# LTC_Sheet.net
KiCad netlist of a schematic drawn in Altium Designer
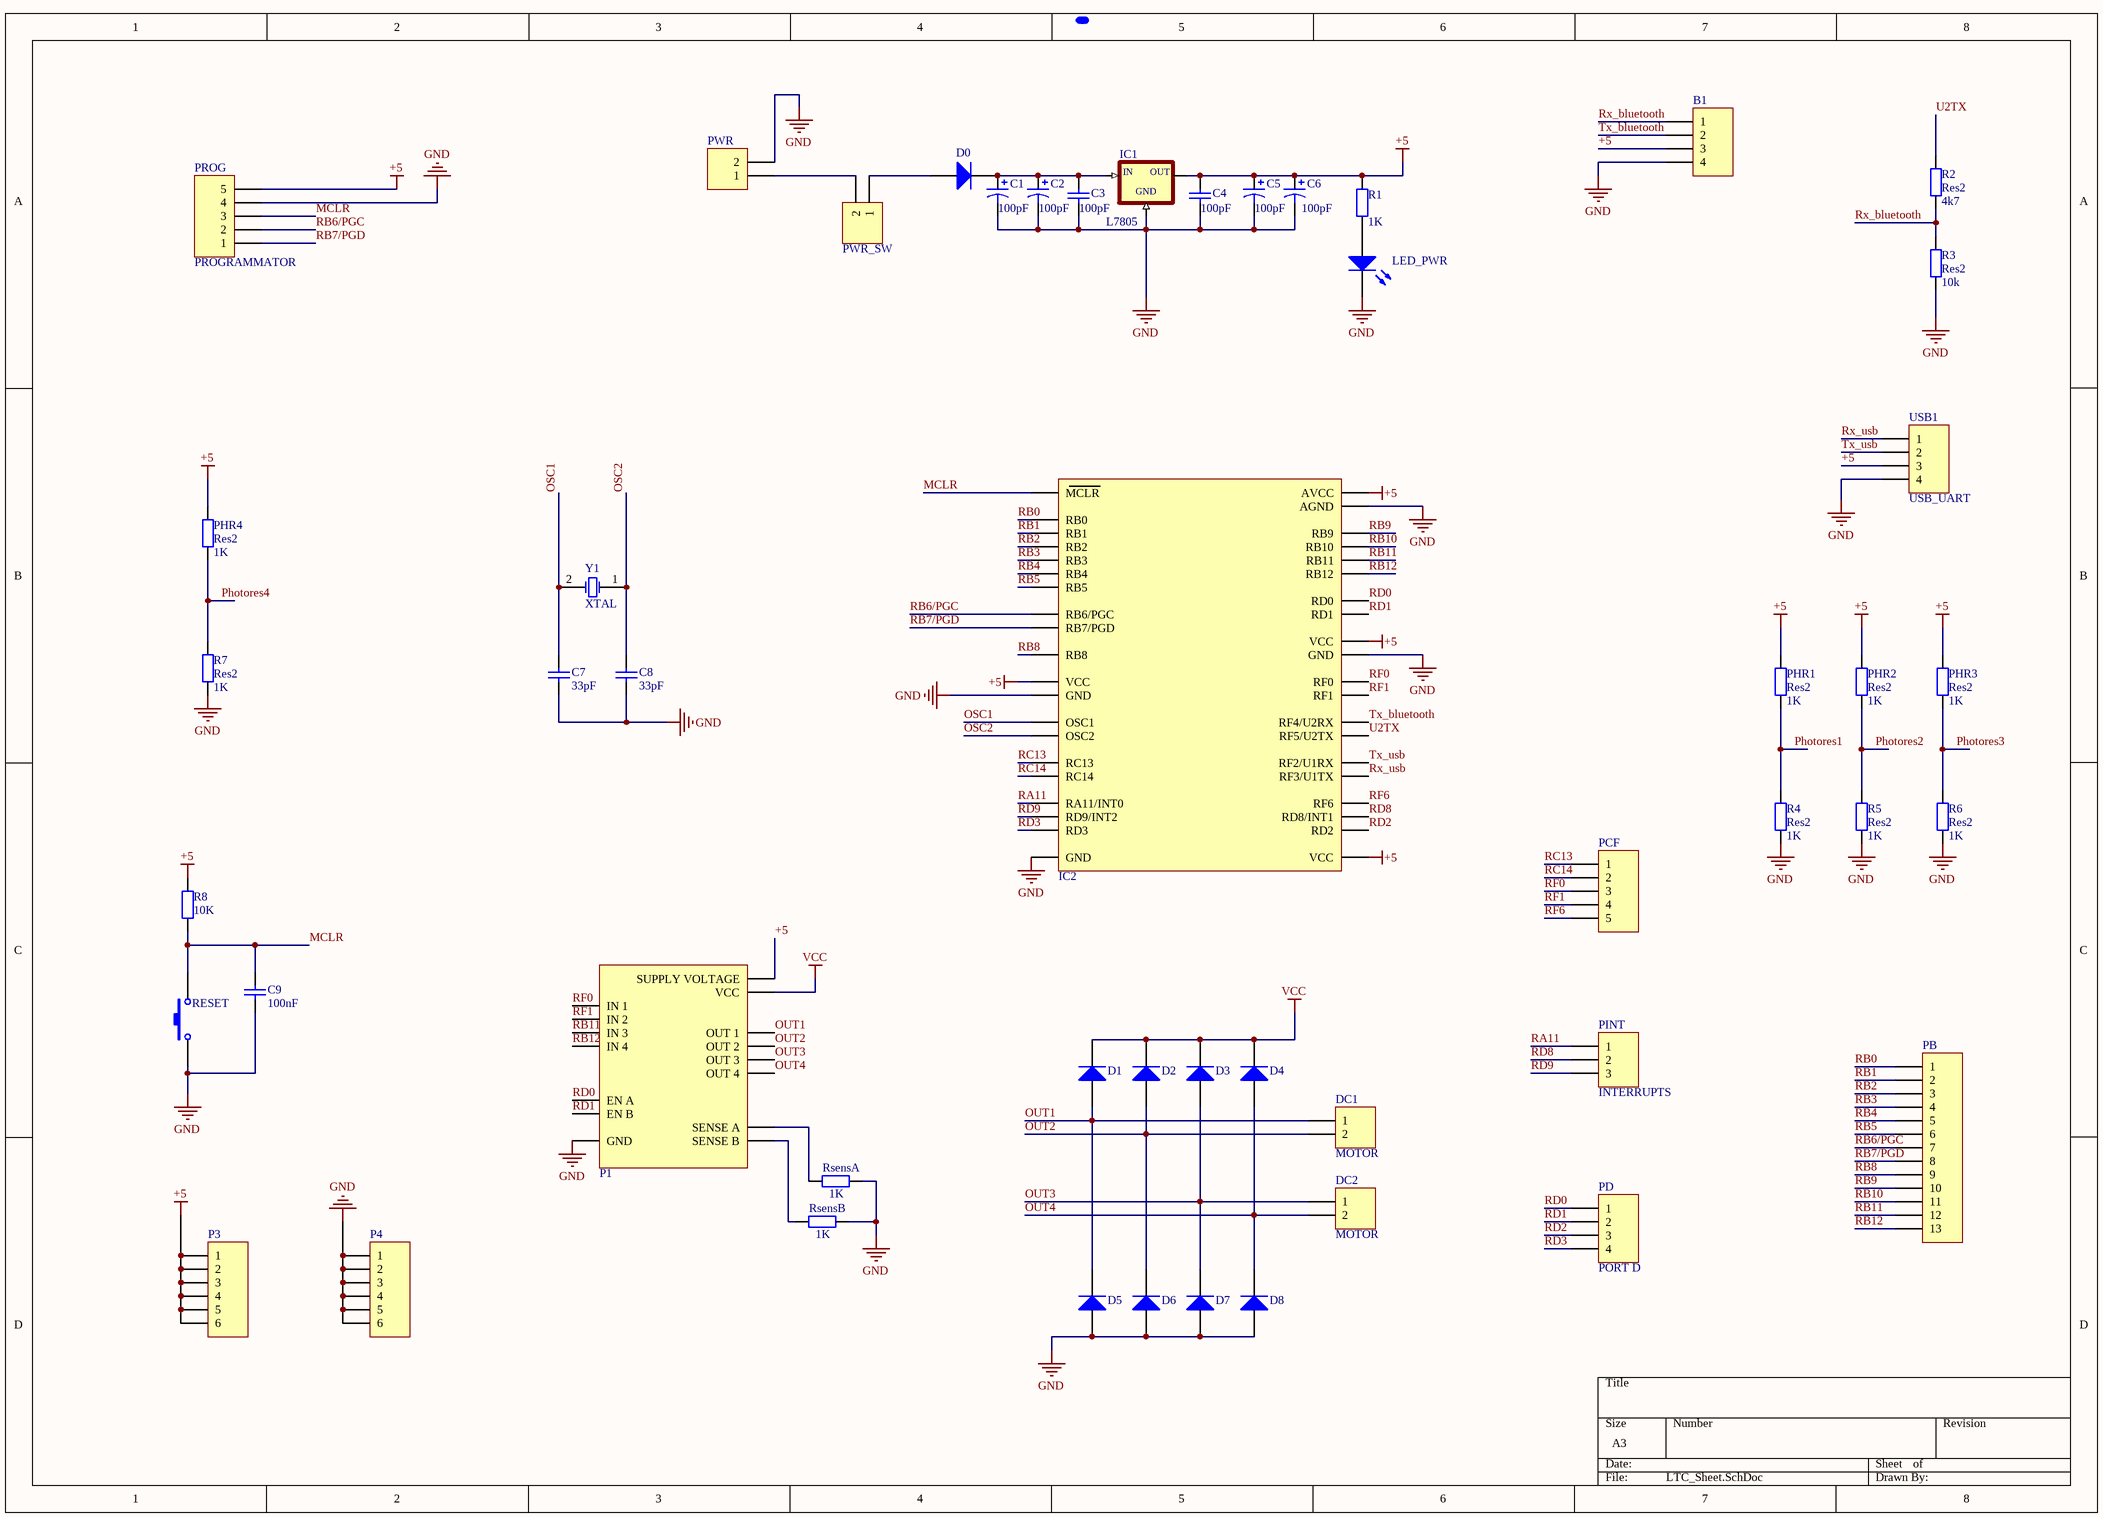
[diagram p0: LTC_Sheet.SchDoc]

(export (version "E")
  (design (tool "Eeschema 10.0.6"))
  (components
    (comp (ref "B1")
      (value "~")
      (footprint "HDR1X4")
      (description "Header, 4-Pin")
      (fields (field (name "PUBLISHER") "Altium Limited"))
      (libsource (lib "Miscellaneous Connectors") (part "Header 4"))
    )
    (comp (ref "C1")
      (value "100pF")
      (footprint "RB7.6-15")
      (description "Polarized Capacitor (Radial)")
      (fields (field (name "PUBLISHER") "Altium Limited"))
      (libsource (lib "Miscellaneous Devices") (part "Cap Pol1"))
    )
    (comp (ref "C2")
      (value "100pF")
      (footprint "RB7.6-15")
      (description "Polarized Capacitor (Radial)")
      (fields (field (name "PUBLISHER") "Altium Limited"))
      (libsource (lib "Miscellaneous Devices") (part "Cap Pol1"))
    )
    (comp (ref "C3")
      (value "100pF")
      (footprint "RAD-0.3")
      (description "Capacitor")
      (fields (field (name "PUBLISHER") "Altium Limited"))
      (libsource (lib "Miscellaneous Devices") (part "Cap"))
    )
    (comp (ref "C4")
      (value "100pF")
      (footprint "RAD-0.3")
      (description "Capacitor")
      (fields (field (name "PUBLISHER") "Altium Limited"))
      (libsource (lib "Miscellaneous Devices") (part "Cap"))
    )
    (comp (ref "C5")
      (value "100pF")
      (footprint "RB7.6-15")
      (description "Polarized Capacitor (Radial)")
      (fields (field (name "PUBLISHER") "Altium Limited"))
      (libsource (lib "Miscellaneous Devices") (part "Cap Pol1"))
    )
    (comp (ref "C6")
      (value "100pF")
      (footprint "RB7.6-15")
      (description "Polarized Capacitor (Radial)")
      (fields (field (name "PUBLISHER") "Altium Limited"))
      (libsource (lib "Miscellaneous Devices") (part "Cap Pol1"))
    )
    (comp (ref "C7")
      (value "33pF")
      (footprint "RAD-0.3")
      (description "Capacitor")
      (fields (field (name "Comment") "Cap") (field (name "PUBLISHER") "Altium Limited"))
      (libsource (lib "Miscellaneous Devices") (part "Cap"))
    )
    (comp (ref "C8")
      (value "33pF")
      (footprint "RAD-0.3")
      (description "Capacitor")
      (fields (field (name "Comment") "Cap") (field (name "PUBLISHER") "Altium Limited"))
      (libsource (lib "Miscellaneous Devices") (part "Cap"))
    )
    (comp (ref "C9")
      (value "100nF")
      (footprint "RAD-0.3")
      (description "Capacitor")
      (fields (field (name "Comment") "Cap") (field (name "PUBLISHER") "Altium Limited"))
      (libsource (lib "Miscellaneous Devices") (part "Cap"))
    )
    (comp (ref "D0")
      (value "~")
      (footprint "DO-41")
      (description "1 Amp General Purpose Rectifier")
      (fields (field (name "PUBLISHER") "Altium Limited"))
      (libsource (lib "Miscellaneous Devices") (part "Diode 1N4007"))
    )
    (comp (ref "D1")
      (value "Diode 1N914")
      (footprint "DO-35")
      (description "High Conductance Fast Diode")
      (fields (field (name "PUBLISHER") "Altium Limited"))
      (libsource (lib "Miscellaneous Devices") (part "Diode 1N914"))
    )
    (comp (ref "D2")
      (value "Diode 1N914")
      (footprint "DO-35")
      (description "High Conductance Fast Diode")
      (fields (field (name "PUBLISHER") "Altium Limited"))
      (libsource (lib "Miscellaneous Devices") (part "Diode 1N914"))
    )
    (comp (ref "D3")
      (value "Diode 1N914")
      (footprint "DO-35")
      (description "High Conductance Fast Diode")
      (fields (field (name "PUBLISHER") "Altium Limited"))
      (libsource (lib "Miscellaneous Devices") (part "Diode 1N914"))
    )
    (comp (ref "D4")
      (value "Diode 1N914")
      (footprint "DO-35")
      (description "High Conductance Fast Diode")
      (fields (field (name "PUBLISHER") "Altium Limited"))
      (libsource (lib "Miscellaneous Devices") (part "Diode 1N914"))
    )
    (comp (ref "D5")
      (value "Diode 1N914")
      (footprint "DO-35")
      (description "High Conductance Fast Diode")
      (fields (field (name "PUBLISHER") "Altium Limited"))
      (libsource (lib "Miscellaneous Devices") (part "Diode 1N914"))
    )
    (comp (ref "D6")
      (value "Diode 1N914")
      (footprint "DO-35")
      (description "High Conductance Fast Diode")
      (fields (field (name "PUBLISHER") "Altium Limited"))
      (libsource (lib "Miscellaneous Devices") (part "Diode 1N914"))
    )
    (comp (ref "D7")
      (value "Diode 1N914")
      (footprint "DO-35")
      (description "High Conductance Fast Diode")
      (fields (field (name "PUBLISHER") "Altium Limited"))
      (libsource (lib "Miscellaneous Devices") (part "Diode 1N914"))
    )
    (comp (ref "D8")
      (value "Diode 1N914")
      (footprint "DO-35")
      (description "High Conductance Fast Diode")
      (fields (field (name "PUBLISHER") "Altium Limited"))
      (libsource (lib "Miscellaneous Devices") (part "Diode 1N914"))
    )
    (comp (ref "DC1")
      (value "MOTOR")
      (footprint "HDR1X2")
      (description "Header, 2-Pin")
      (fields (field (name "PUBLISHER") "Altium Limited"))
      (libsource (lib "") (part "Header 2_2"))
    )
    (comp (ref "DC2")
      (value "MOTOR")
      (footprint "HDR1X2")
      (description "Header, 2-Pin")
      (fields (field (name "PUBLISHER") "Altium Limited"))
      (libsource (lib "") (part "Header 2_2"))
    )
    (comp (ref "IC1")
      (value "L7805")
      (footprint "78XXS")
      (description "Linear Voltage Regulator IC 1 Output 1.5A D2PAK")
      (fields (field (name "MF") "STMicroelectronics"))
      (libsource (lib "L7805") (part "L7805"))
    )
    (comp (ref "IC2") (value "dsPIC30F4013") (libsource (lib "LibLTC") (part "IC_40")))
    (comp (ref "LED_PWR")
      (value "~")
      (footprint "LED-1")
      (description "Typical RED GaAs LED")
      (fields (field (name "PUBLISHER") "Altium Limited"))
      (libsource (lib "Miscellaneous Devices") (part "LED1"))
    )
    (comp (ref "P1") (value "L298N") (libsource (lib "LibRC") (part "L298N")))
    (comp (ref "P3")
      (value "~")
      (footprint "HDR1X6")
      (description "Header, 6-Pin")
      (fields (field (name "PUBLISHER") "Altium Limited"))
      (libsource (lib "Miscellaneous Connectors") (part "Header 6"))
    )
    (comp (ref "P4")
      (value "~")
      (footprint "HDR1X6")
      (description "Header, 6-Pin")
      (fields (field (name "PUBLISHER") "Altium Limited"))
      (libsource (lib "Miscellaneous Connectors") (part "Header 6"))
    )
    (comp (ref "PB")
      (value "~")
      (footprint "HDR1X13")
      (description "Header, 13-Pin")
      (fields (field (name "PUBLISHER") "Altium Limited"))
      (libsource (lib "Miscellaneous Connectors") (part "Header 13"))
    )
    (comp (ref "PCF")
      (value "~")
      (footprint "HDR1X5")
      (description "Header, 5-Pin")
      (fields (field (name "PUBLISHER") "Altium Limited"))
      (libsource (lib "") (part "Header 5_1"))
    )
    (comp (ref "PD")
      (value "PORT D")
      (footprint "HDR1X4")
      (description "Header, 4-Pin")
      (fields (field (name "PUBLISHER") "Altium Limited"))
      (libsource (lib "Miscellaneous Connectors") (part "Header 4"))
    )
    (comp (ref "PHR1")
      (value "Res2")
      (footprint "AXIAL-0.4")
      (description "Resistor")
      (fields (field (name "ALTIUM_VALUE") "1K") (field (name "PUBLISHER") "Altium Limited"))
      (libsource (lib "Miscellaneous Devices") (part "Res2"))
    )
    (comp (ref "PHR2")
      (value "Res2")
      (footprint "AXIAL-0.4")
      (description "Resistor")
      (fields (field (name "ALTIUM_VALUE") "1K") (field (name "PUBLISHER") "Altium Limited"))
      (libsource (lib "Miscellaneous Devices") (part "Res2"))
    )
    (comp (ref "PHR3")
      (value "Res2")
      (footprint "AXIAL-0.4")
      (description "Resistor")
      (fields (field (name "ALTIUM_VALUE") "1K") (field (name "PUBLISHER") "Altium Limited"))
      (libsource (lib "Miscellaneous Devices") (part "Res2"))
    )
    (comp (ref "PHR4")
      (value "Res2")
      (footprint "AXIAL-0.4")
      (description "Resistor")
      (fields (field (name "ALTIUM_VALUE") "1K") (field (name "PUBLISHER") "Altium Limited"))
      (libsource (lib "Miscellaneous Devices") (part "Res2"))
    )
    (comp (ref "PINT")
      (value "INTERRUPTS")
      (footprint "HDR1X3")
      (description "Header, 3-Pin")
      (fields (field (name "PUBLISHER") "Altium Limited"))
      (libsource (lib "Miscellaneous Connectors") (part "Header 3"))
    )
    (comp (ref "PROG")
      (value "PROGRAMMATOR")
      (footprint "HDR1X5")
      (description "Header, 5-Pin")
      (fields (field (name "PUBLISHER") "Altium Limited"))
      (libsource (lib "Miscellaneous Connectors") (part "Header 5"))
    )
    (comp (ref "PWR")
      (value "Header 2")
      (footprint "HDR1X2")
      (description "Header, 2-Pin")
      (fields (field (name "PUBLISHER") "Altium Limited"))
      (libsource (lib "Miscellaneous Connectors") (part "Header 2"))
    )
    (comp (ref "PWR_SW")
      (value "Header 2")
      (footprint "HDR1X2")
      (description "Header, 2-Pin")
      (fields (field (name "PUBLISHER") "Altium Limited"))
      (libsource (lib "") (part "Header 2_1"))
    )
    (comp (ref "R1")
      (value "1K")
      (footprint "AXIAL-0.4")
      (description "Resistor")
      (fields (field (name "PUBLISHER") "Altium Limited"))
      (libsource (lib "Miscellaneous Devices") (part "Res2"))
    )
    (comp (ref "R2")
      (value "Res2")
      (footprint "AXIAL-0.4")
      (description "Resistor")
      (fields (field (name "ALTIUM_VALUE") "4k7") (field (name "PUBLISHER") "Altium Limited"))
      (libsource (lib "Miscellaneous Devices") (part "Res2"))
    )
    (comp (ref "R3")
      (value "Res2")
      (footprint "AXIAL-0.4")
      (description "Resistor")
      (fields (field (name "ALTIUM_VALUE") "10k") (field (name "PUBLISHER") "Altium Limited"))
      (libsource (lib "Miscellaneous Devices") (part "Res2"))
    )
    (comp (ref "R4")
      (value "Res2")
      (footprint "AXIAL-0.4")
      (description "Resistor")
      (fields (field (name "ALTIUM_VALUE") "1K") (field (name "PUBLISHER") "Altium Limited"))
      (libsource (lib "Miscellaneous Devices") (part "Res2"))
    )
    (comp (ref "R5")
      (value "Res2")
      (footprint "AXIAL-0.4")
      (description "Resistor")
      (fields (field (name "ALTIUM_VALUE") "1K") (field (name "PUBLISHER") "Altium Limited"))
      (libsource (lib "Miscellaneous Devices") (part "Res2"))
    )
    (comp (ref "R6")
      (value "Res2")
      (footprint "AXIAL-0.4")
      (description "Resistor")
      (fields (field (name "ALTIUM_VALUE") "1K") (field (name "PUBLISHER") "Altium Limited"))
      (libsource (lib "Miscellaneous Devices") (part "Res2"))
    )
    (comp (ref "R7")
      (value "Res2")
      (footprint "AXIAL-0.4")
      (description "Resistor")
      (fields (field (name "ALTIUM_VALUE") "1K") (field (name "PUBLISHER") "Altium Limited"))
      (libsource (lib "Miscellaneous Devices") (part "Res2"))
    )
    (comp (ref "R8")
      (value "10K")
      (footprint "AXIAL-0.4")
      (description "Resistor")
      (fields (field (name "Comment") "Res2") (field (name "PUBLISHER") "Altium Limited"))
      (libsource (lib "Miscellaneous Devices") (part "Res2"))
    )
    (comp (ref "RESET")
      (value "SW-PB")
      (footprint "SPST-2")
      (description "Switch")
      (fields (field (name "PUBLISHER") "Altium Limited"))
      (libsource (lib "Miscellaneous Devices") (part "SW-PB"))
    )
    (comp (ref "RsensA")
      (value "1K")
      (footprint "AXIAL-0.4")
      (description "Resistor")
      (fields (field (name "PUBLISHER") "Altium Limited"))
      (libsource (lib "") (part "Res2_1"))
    )
    (comp (ref "RsensB")
      (value "1K")
      (footprint "AXIAL-0.4")
      (description "Resistor")
      (fields (field (name "PUBLISHER") "Altium Limited"))
      (libsource (lib "") (part "Res2_1"))
    )
    (comp (ref "USB1")
      (value "USB_UART")
      (footprint "HDR1X4")
      (description "Header, 4-Pin")
      (fields (field (name "PUBLISHER") "Altium Limited"))
      (libsource (lib "Miscellaneous Connectors") (part "Header 4"))
    )
    (comp (ref "Y1")
      (value "XTAL")
      (footprint "R38")
      (description "Crystal Oscillator")
      (fields (field (name "PUBLISHER") "Altium Limited"))
      (libsource (lib "Miscellaneous Devices") (part "XTAL"))
    )
  )
  (nets
    (net (code "1") (name "+5") (class "Default")
      (node (ref "B1") (pin "3") (pinfunction "3_3") (pintype "passive"))
      (node (ref "C4") (pin "2") (pinfunction "2_2") (pintype "passive"))
      (node (ref "C5") (pin "1") (pinfunction "1_1") (pintype "passive"))
      (node (ref "C6") (pin "1") (pinfunction "1_1") (pintype "passive"))
      (node (ref "IC1") (pin "OUT") (pinfunction "OUT_OUT") (pintype "passive"))
      (node (ref "IC2") (pin "11") (pinfunction "VCC_11") (pintype "passive"))
      (node (ref "IC2") (pin "21") (pinfunction "VCC_21") (pintype "passive"))
      (node (ref "IC2") (pin "32") (pinfunction "VCC_32") (pintype "passive"))
      (node (ref "IC2") (pin "40") (pinfunction "AVCC_40") (pintype "passive"))
      (node (ref "P1") (pin "4") (pinfunction "SUPPLY_VOLTAGE_4") (pintype "passive"))
      (node (ref "P3") (pin "1") (pinfunction "1_1") (pintype "passive"))
      (node (ref "P3") (pin "2") (pinfunction "2_2") (pintype "passive"))
      (node (ref "P3") (pin "3") (pinfunction "3_3") (pintype "passive"))
      (node (ref "P3") (pin "4") (pinfunction "4_4") (pintype "passive"))
      (node (ref "P3") (pin "5") (pinfunction "5_5") (pintype "passive"))
      (node (ref "P3") (pin "6") (pinfunction "6_6") (pintype "passive"))
      (node (ref "PHR1") (pin "2") (pinfunction "2_2") (pintype "passive"))
      (node (ref "PHR2") (pin "2") (pinfunction "2_2") (pintype "passive"))
      (node (ref "PHR3") (pin "2") (pinfunction "2_2") (pintype "passive"))
      (node (ref "PHR4") (pin "2") (pinfunction "2_2") (pintype "passive"))
      (node (ref "PROG") (pin "5") (pinfunction "5_5") (pintype "passive"))
      (node (ref "R1") (pin "2") (pinfunction "2_2") (pintype "passive"))
      (node (ref "R8") (pin "2") (pinfunction "2_2") (pintype "passive"))
      (node (ref "USB1") (pin "3") (pinfunction "3_3") (pintype "passive"))
    )
    (net (code "2") (name "/MCLR") (class "Default")
      (node (ref "C9") (pin "1") (pinfunction "1_1") (pintype "passive"))
      (node (ref "IC2") (pin "1") (pinfunction "MCLR_1") (pintype "passive"))
      (node (ref "PROG") (pin "3") (pinfunction "3_3") (pintype "passive"))
      (node (ref "R8") (pin "1") (pinfunction "1_1") (pintype "passive"))
      (node (ref "RESET") (pin "2") (pinfunction "2_2") (pintype "passive"))
    )
    (net (code "3") (name "/OSC1") (class "Default")
      (node (ref "C7") (pin "2") (pinfunction "2_2") (pintype "passive"))
      (node (ref "IC2") (pin "13") (pinfunction "OSC1_13") (pintype "passive"))
      (node (ref "Y1") (pin "2") (pinfunction "OSC2_2") (pintype "passive"))
    )
    (net (code "4") (name "/OSC2") (class "Default")
      (node (ref "C8") (pin "2") (pinfunction "2_2") (pintype "passive"))
      (node (ref "IC2") (pin "14") (pinfunction "OSC2_14") (pintype "passive"))
      (node (ref "Y1") (pin "1") (pinfunction "OSC1_1") (pintype "passive"))
    )
    (net (code "5") (name "/OUT1") (class "Default")
      (node (ref "D1") (pin "1") (pinfunction "A_1") (pintype "passive"))
      (node (ref "D5") (pin "2") (pinfunction "K_2") (pintype "passive"))
      (node (ref "DC1") (pin "1") (pinfunction "1_1") (pintype "passive"))
      (node (ref "P1") (pin "2") (pinfunction "OUT_1_2") (pintype "passive"))
    )
    (net (code "6") (name "/OUT2") (class "Default")
      (node (ref "D2") (pin "1") (pinfunction "A_1") (pintype "passive"))
      (node (ref "D6") (pin "2") (pinfunction "K_2") (pintype "passive"))
      (node (ref "DC1") (pin "2") (pinfunction "2_2") (pintype "passive"))
      (node (ref "P1") (pin "3") (pinfunction "OUT_2_3") (pintype "passive"))
    )
    (net (code "7") (name "/OUT3") (class "Default")
      (node (ref "D3") (pin "1") (pinfunction "A_1") (pintype "passive"))
      (node (ref "D7") (pin "2") (pinfunction "K_2") (pintype "passive"))
      (node (ref "DC2") (pin "1") (pinfunction "1_1") (pintype "passive"))
      (node (ref "P1") (pin "13") (pinfunction "OUT_3_13") (pintype "passive"))
    )
    (net (code "8") (name "/OUT4") (class "Default")
      (node (ref "D4") (pin "1") (pinfunction "A_1") (pintype "passive"))
      (node (ref "D8") (pin "2") (pinfunction "K_2") (pintype "passive"))
      (node (ref "DC2") (pin "2") (pinfunction "2_2") (pintype "passive"))
      (node (ref "P1") (pin "14") (pinfunction "OUT_4_14") (pintype "passive"))
    )
    (net (code "9") (name "/Photores1") (class "Default")
      (node (ref "PHR1") (pin "1") (pinfunction "1_1") (pintype "passive"))
      (node (ref "R4") (pin "2") (pinfunction "2_2") (pintype "passive"))
    )
    (net (code "10") (name "/Photores2") (class "Default")
      (node (ref "PHR2") (pin "1") (pinfunction "1_1") (pintype "passive"))
      (node (ref "R5") (pin "2") (pinfunction "2_2") (pintype "passive"))
    )
    (net (code "11") (name "/Photores3") (class "Default")
      (node (ref "PHR3") (pin "1") (pinfunction "1_1") (pintype "passive"))
      (node (ref "R6") (pin "2") (pinfunction "2_2") (pintype "passive"))
    )
    (net (code "12") (name "/Photores4") (class "Default")
      (node (ref "PHR4") (pin "1") (pinfunction "1_1") (pintype "passive"))
      (node (ref "R7") (pin "2") (pinfunction "2_2") (pintype "passive"))
    )
    (net (code "13") (name "/RA11") (class "Default")
      (node (ref "IC2") (pin "17") (pinfunction "RA11/INT0_17") (pintype "passive"))
      (node (ref "PINT") (pin "1") (pinfunction "1_1") (pintype "passive"))
    )
    (net (code "14") (name "/RB0") (class "Default")
      (node (ref "IC2") (pin "2") (pinfunction "RB0_2") (pintype "passive"))
      (node (ref "PB") (pin "1") (pinfunction "1_1") (pintype "passive"))
    )
    (net (code "15") (name "/RB1") (class "Default")
      (node (ref "IC2") (pin "3") (pinfunction "RB1_3") (pintype "passive"))
      (node (ref "PB") (pin "2") (pinfunction "2_2") (pintype "passive"))
    )
    (net (code "16") (name "/RB2") (class "Default")
      (node (ref "IC2") (pin "4") (pinfunction "RB2_4") (pintype "passive"))
      (node (ref "PB") (pin "3") (pinfunction "3_3") (pintype "passive"))
    )
    (net (code "17") (name "/RB3") (class "Default")
      (node (ref "IC2") (pin "5") (pinfunction "RB3_5") (pintype "passive"))
      (node (ref "PB") (pin "4") (pinfunction "4_4") (pintype "passive"))
    )
    (net (code "18") (name "/RB4") (class "Default")
      (node (ref "IC2") (pin "6") (pinfunction "RB4_6") (pintype "passive"))
      (node (ref "PB") (pin "5") (pinfunction "5_5") (pintype "passive"))
    )
    (net (code "19") (name "/RB5") (class "Default")
      (node (ref "IC2") (pin "7") (pinfunction "RB5_7") (pintype "passive"))
      (node (ref "PB") (pin "6") (pinfunction "6_6") (pintype "passive"))
    )
    (net (code "20") (name "/RB6{slash}PGC") (class "Default")
      (node (ref "IC2") (pin "8") (pinfunction "RB6/PGC_8") (pintype "passive"))
      (node (ref "PB") (pin "7") (pinfunction "7_7") (pintype "passive"))
      (node (ref "PROG") (pin "2") (pinfunction "2_2") (pintype "passive"))
    )
    (net (code "21") (name "/RB7{slash}PGD") (class "Default")
      (node (ref "IC2") (pin "9") (pinfunction "RB7/PGD_9") (pintype "passive"))
      (node (ref "PB") (pin "8") (pinfunction "8_8") (pintype "passive"))
      (node (ref "PROG") (pin "1") (pinfunction "1_1") (pintype "passive"))
    )
    (net (code "22") (name "/RB8") (class "Default")
      (node (ref "IC2") (pin "10") (pinfunction "RB8_10") (pintype "passive"))
      (node (ref "PB") (pin "9") (pinfunction "9_9") (pintype "passive"))
    )
    (net (code "23") (name "/RB9") (class "Default")
      (node (ref "IC2") (pin "38") (pinfunction "RB9_38") (pintype "passive"))
      (node (ref "PB") (pin "10") (pinfunction "10_10") (pintype "passive"))
    )
    (net (code "24") (name "/RB10") (class "Default")
      (node (ref "IC2") (pin "37") (pinfunction "RB10_37") (pintype "passive"))
      (node (ref "PB") (pin "11") (pinfunction "11_11") (pintype "passive"))
    )
    (net (code "25") (name "/RB11") (class "Default")
      (node (ref "IC2") (pin "36") (pinfunction "RB11_36") (pintype "passive"))
      (node (ref "P1") (pin "10") (pinfunction "IN_3_10") (pintype "passive"))
      (node (ref "PB") (pin "12") (pinfunction "12_12") (pintype "passive"))
    )
    (net (code "26") (name "/RB12") (class "Default")
      (node (ref "IC2") (pin "35") (pinfunction "RB12_35") (pintype "passive"))
      (node (ref "P1") (pin "12") (pinfunction "IN_4_12") (pintype "passive"))
      (node (ref "PB") (pin "13") (pinfunction "13_13") (pintype "passive"))
    )
    (net (code "27") (name "/RC13") (class "Default")
      (node (ref "IC2") (pin "15") (pinfunction "RC13_15") (pintype "passive"))
      (node (ref "PCF") (pin "1") (pinfunction "1_1") (pintype "passive"))
    )
    (net (code "28") (name "/RC14") (class "Default")
      (node (ref "IC2") (pin "16") (pinfunction "RC14_16") (pintype "passive"))
      (node (ref "PCF") (pin "2") (pinfunction "2_2") (pintype "passive"))
    )
    (net (code "29") (name "/RD0") (class "Default")
      (node (ref "IC2") (pin "34") (pinfunction "RD0_34") (pintype "passive"))
      (node (ref "P1") (pin "6") (pinfunction "EN_A_6") (pintype "passive"))
      (node (ref "PD") (pin "1") (pinfunction "1_1") (pintype "passive"))
    )
    (net (code "30") (name "/RD1") (class "Default")
      (node (ref "IC2") (pin "33") (pinfunction "RD1_33") (pintype "passive"))
      (node (ref "P1") (pin "11") (pinfunction "EN_B_11") (pintype "passive"))
      (node (ref "PD") (pin "2") (pinfunction "2_2") (pintype "passive"))
    )
    (net (code "31") (name "/RD2") (class "Default")
      (node (ref "IC2") (pin "22") (pinfunction "RD2_22") (pintype "passive"))
      (node (ref "PD") (pin "3") (pinfunction "3_3") (pintype "passive"))
    )
    (net (code "32") (name "/RD3") (class "Default")
      (node (ref "IC2") (pin "19") (pinfunction "RD3_19") (pintype "passive"))
      (node (ref "PD") (pin "4") (pinfunction "4_4") (pintype "passive"))
    )
    (net (code "33") (name "/RD8") (class "Default")
      (node (ref "IC2") (pin "23") (pinfunction "RD8/INT1_23") (pintype "passive"))
      (node (ref "PINT") (pin "2") (pinfunction "2_2") (pintype "passive"))
    )
    (net (code "34") (name "/RD9") (class "Default")
      (node (ref "IC2") (pin "18") (pinfunction "RD9/INT2_18") (pintype "passive"))
      (node (ref "PINT") (pin "3") (pinfunction "3_3") (pintype "passive"))
    )
    (net (code "35") (name "/RF0") (class "Default")
      (node (ref "IC2") (pin "30") (pinfunction "RF0_30") (pintype "passive"))
      (node (ref "P1") (pin "5") (pinfunction "IN_1_5") (pintype "passive"))
      (node (ref "PCF") (pin "3") (pinfunction "3_3") (pintype "passive"))
    )
    (net (code "36") (name "/RF1") (class "Default")
      (node (ref "IC2") (pin "29") (pinfunction "RF1_29") (pintype "passive"))
      (node (ref "P1") (pin "7") (pinfunction "IN_2_7") (pintype "passive"))
      (node (ref "PCF") (pin "4") (pinfunction "4_4") (pintype "passive"))
    )
    (net (code "37") (name "/RF6") (class "Default")
      (node (ref "IC2") (pin "24") (pinfunction "RF6_24") (pintype "passive"))
      (node (ref "PCF") (pin "5") (pinfunction "5_5") (pintype "passive"))
    )
    (net (code "38") (name "/Rx_bluetooth") (class "Default")
      (node (ref "B1") (pin "1") (pinfunction "1_1") (pintype "passive"))
      (node (ref "R2") (pin "1") (pinfunction "1_1") (pintype "passive"))
      (node (ref "R3") (pin "2") (pinfunction "2_2") (pintype "passive"))
    )
    (net (code "39") (name "/Rx_usb") (class "Default")
      (node (ref "IC2") (pin "25") (pinfunction "RF3/U1TX_25") (pintype "passive"))
      (node (ref "USB1") (pin "1") (pinfunction "1_1") (pintype "passive"))
    )
    (net (code "40") (name "/Tx_bluetooth") (class "Default")
      (node (ref "B1") (pin "2") (pinfunction "2_2") (pintype "passive"))
      (node (ref "IC2") (pin "28") (pinfunction "RF4/U2RX_28") (pintype "passive"))
    )
    (net (code "41") (name "/Tx_usb") (class "Default")
      (node (ref "IC2") (pin "26") (pinfunction "RF2/U1RX_26") (pintype "passive"))
      (node (ref "USB1") (pin "2") (pinfunction "2_2") (pintype "passive"))
    )
    (net (code "42") (name "/U2TX") (class "Default")
      (node (ref "IC2") (pin "27") (pinfunction "RF5/U2TX_27") (pintype "passive"))
      (node (ref "R2") (pin "2") (pinfunction "2_2") (pintype "passive"))
    )
    (net (code "43") (name "GND") (class "Default")
      (node (ref "B1") (pin "4") (pinfunction "4_4") (pintype "passive"))
      (node (ref "C1") (pin "2") (pinfunction "2_2") (pintype "passive"))
      (node (ref "C2") (pin "2") (pinfunction "2_2") (pintype "passive"))
      (node (ref "C3") (pin "1") (pinfunction "1_1") (pintype "passive"))
      (node (ref "C4") (pin "1") (pinfunction "1_1") (pintype "passive"))
      (node (ref "C5") (pin "2") (pinfunction "2_2") (pintype "passive"))
      (node (ref "C6") (pin "2") (pinfunction "2_2") (pintype "passive"))
      (node (ref "C7") (pin "1") (pinfunction "1_1") (pintype "passive"))
      (node (ref "C8") (pin "1") (pinfunction "1_1") (pintype "passive"))
      (node (ref "C9") (pin "2") (pinfunction "2_2") (pintype "passive"))
      (node (ref "D5") (pin "1") (pinfunction "A_1") (pintype "passive"))
      (node (ref "D6") (pin "1") (pinfunction "A_1") (pintype "passive"))
      (node (ref "D7") (pin "1") (pinfunction "A_1") (pintype "passive"))
      (node (ref "D8") (pin "1") (pinfunction "A_1") (pintype "passive"))
      (node (ref "IC1") (pin "GND") (pinfunction "GND_GND") (pintype "input"))
      (node (ref "IC2") (pin "12") (pinfunction "GND_12") (pintype "passive"))
      (node (ref "IC2") (pin "20") (pinfunction "GND_20") (pintype "passive"))
      (node (ref "IC2") (pin "31") (pinfunction "GND_31") (pintype "passive"))
      (node (ref "IC2") (pin "39") (pinfunction "AGND_39") (pintype "passive"))
      (node (ref "LED_PWR") (pin "2") (pinfunction "K_2") (pintype "passive"))
      (node (ref "P1") (pin "8") (pinfunction "GND_8") (pintype "passive"))
      (node (ref "P4") (pin "1") (pinfunction "1_1") (pintype "passive"))
      (node (ref "P4") (pin "2") (pinfunction "2_2") (pintype "passive"))
      (node (ref "P4") (pin "3") (pinfunction "3_3") (pintype "passive"))
      (node (ref "P4") (pin "4") (pinfunction "4_4") (pintype "passive"))
      (node (ref "P4") (pin "5") (pinfunction "5_5") (pintype "passive"))
      (node (ref "P4") (pin "6") (pinfunction "6_6") (pintype "passive"))
      (node (ref "PROG") (pin "4") (pinfunction "4_4") (pintype "passive"))
      (node (ref "PWR") (pin "2") (pinfunction "2_2") (pintype "passive"))
      (node (ref "R3") (pin "1") (pinfunction "1_1") (pintype "passive"))
      (node (ref "R4") (pin "1") (pinfunction "1_1") (pintype "passive"))
      (node (ref "R5") (pin "1") (pinfunction "1_1") (pintype "passive"))
      (node (ref "R6") (pin "1") (pinfunction "1_1") (pintype "passive"))
      (node (ref "R7") (pin "1") (pinfunction "1_1") (pintype "passive"))
      (node (ref "RESET") (pin "1") (pinfunction "1_1") (pintype "passive"))
      (node (ref "RsensA") (pin "2") (pinfunction "2_2") (pintype "passive"))
      (node (ref "RsensB") (pin "2") (pinfunction "2_2") (pintype "passive"))
      (node (ref "USB1") (pin "4") (pinfunction "4_4") (pintype "passive"))
    )
    (net (code "44") (name "Net-(D0-A)") (class "Default")
      (node (ref "D0") (pin "1") (pinfunction "A_1") (pintype "passive"))
      (node (ref "PWR_SW") (pin "1") (pinfunction "1_1") (pintype "passive"))
    )
    (net (code "45") (name "Net-(D0-K)") (class "Default")
      (node (ref "C1") (pin "1") (pinfunction "1_1") (pintype "passive"))
      (node (ref "C2") (pin "1") (pinfunction "1_1") (pintype "passive"))
      (node (ref "C3") (pin "2") (pinfunction "2_2") (pintype "passive"))
      (node (ref "D0") (pin "2") (pinfunction "K_2") (pintype "passive"))
      (node (ref "IC1") (pin "IN") (pinfunction "IN_IN") (pintype "input"))
    )
    (net (code "46") (name "Net-(LED_PWR-A)") (class "Default")
      (node (ref "LED_PWR") (pin "1") (pinfunction "A_1") (pintype "passive"))
      (node (ref "R1") (pin "1") (pinfunction "1_1") (pintype "passive"))
    )
    (net (code "47") (name "Net-(P1-SENSE_A)") (class "Default")
      (node (ref "P1") (pin "1") (pinfunction "SENSE_A_1") (pintype "passive"))
      (node (ref "RsensA") (pin "1") (pinfunction "1_1") (pintype "passive"))
    )
    (net (code "48") (name "Net-(P1-SENSE_B)") (class "Default")
      (node (ref "P1") (pin "15") (pinfunction "SENSE_B_15") (pintype "passive"))
      (node (ref "RsensB") (pin "1") (pinfunction "1_1") (pintype "passive"))
    )
    (net (code "49") (name "Net-(PWR-Pad1)") (class "Default")
      (node (ref "PWR") (pin "1") (pinfunction "1_1") (pintype "passive"))
      (node (ref "PWR_SW") (pin "2") (pinfunction "2_2") (pintype "passive"))
    )
    (net (code "50") (name "VCC") (class "Default")
      (node (ref "D1") (pin "2") (pinfunction "K_2") (pintype "passive"))
      (node (ref "D2") (pin "2") (pinfunction "K_2") (pintype "passive"))
      (node (ref "D3") (pin "2") (pinfunction "K_2") (pintype "passive"))
      (node (ref "D4") (pin "2") (pinfunction "K_2") (pintype "passive"))
      (node (ref "P1") (pin "9") (pinfunction "VCC_9") (pintype "passive"))
    )
  )
)
